# ProPrj___2026-04-10.net
KiCad netlist of a schematic drawn in EasyEDA Pro
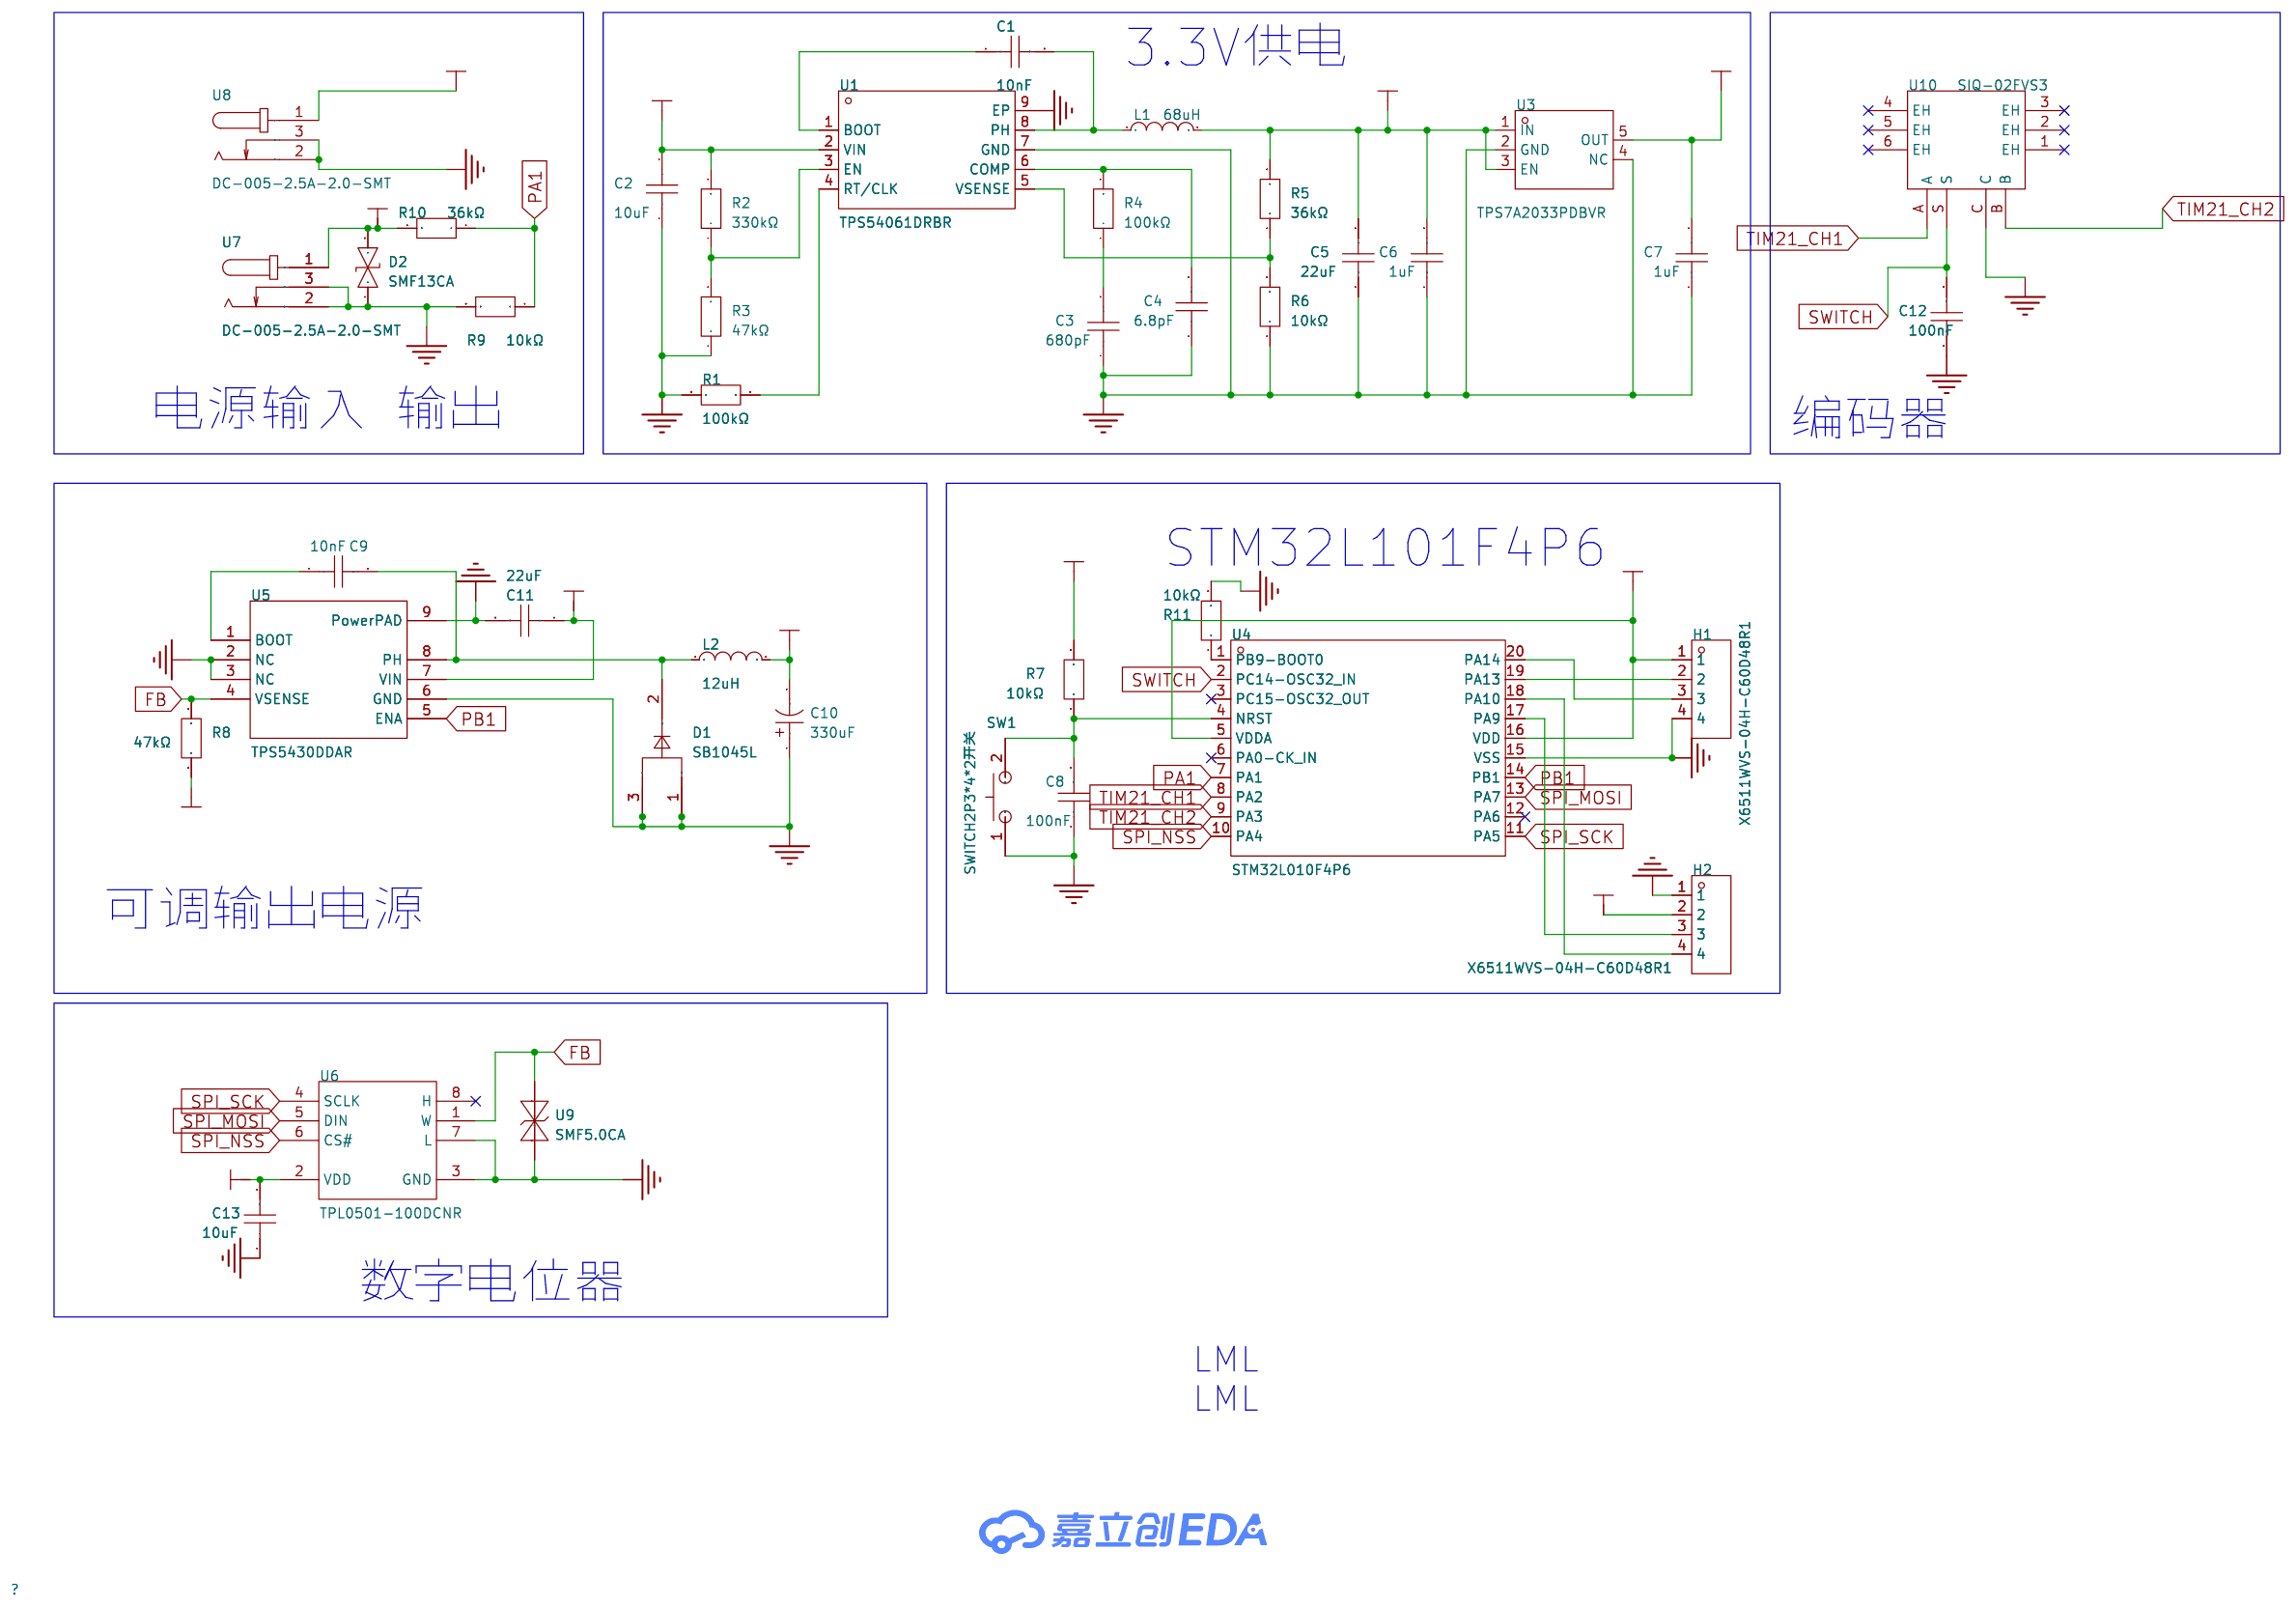
[diagram p0: schematic sheet]

(export (version "E")
  (design (tool "Eeschema 10.0.6"))
  (components
    (comp (ref "C1")
      (value "10nF")
      (footprint "easyedapro:C0603")
      (description "容值:10nF;精度:±10%;额定电压:50V;温度系数:X7R;")
      (fields
        (field (name "Manufacturer Part") "AC0603KPX7R9BB103")
        (field (name "Manufacturer") "YAGEO(国巨)")
      )
      (libsource (lib "easyedapro") (part "AC0603KPX7R9BB103"))
    )
    (comp (ref "C2")
      (value "10uF")
      (footprint "easyedapro:C0603")
      (description "容值:4.7uF;精度:±10%;额定电压:16V;温度系数:X7R;")
      (fields
        (field (name "Manufacturer Part") "GRM188Z71C475KE21J")
        (field (name "Manufacturer") "muRata(村田)")
      )
      (libsource (lib "easyedapro") (part "GRM188Z71C475KE21J"))
    )
    (comp (ref "C3")
      (value "680pF")
      (footprint "easyedapro:C0603")
      (description "容值:4.7uF;精度:±10%;额定电压:16V;温度系数:X7R;")
      (fields
        (field (name "Manufacturer Part") "GRM188Z71C475KE21J")
        (field (name "Manufacturer") "muRata(村田)")
      )
      (libsource (lib "easyedapro") (part "GRM188Z71C475KE21J"))
    )
    (comp (ref "C4")
      (value "6.8pF")
      (footprint "easyedapro:C0603")
      (description "容值:4.7uF;精度:±10%;额定电压:16V;温度系数:X7R;")
      (fields
        (field (name "Manufacturer Part") "GRM188Z71C475KE21J")
        (field (name "Manufacturer") "muRata(村田)")
      )
      (libsource (lib "easyedapro") (part "GRM188Z71C475KE21J"))
    )
    (comp (ref "C5")
      (value "22uF")
      (footprint "easyedapro:C0603")
      (description "容值:4.7uF;精度:±10%;额定电压:16V;温度系数:X7R;")
      (fields
        (field (name "Manufacturer Part") "GRM188Z71C475KE21J")
        (field (name "Manufacturer") "muRata(村田)")
      )
      (libsource (lib "easyedapro") (part "GRM188Z71C475KE21J"))
    )
    (comp (ref "C6")
      (value "1uF")
      (footprint "easyedapro:C0603")
      (description "容值:4.7uF;精度:±10%;额定电压:16V;温度系数:X7R;")
      (fields
        (field (name "Manufacturer Part") "GRM188Z71C475KE21J")
        (field (name "Manufacturer") "muRata(村田)")
      )
      (libsource (lib "easyedapro") (part "GRM188Z71C475KE21J"))
    )
    (comp (ref "C7")
      (value "1uF")
      (footprint "easyedapro:C0603")
      (description "容值:4.7uF;精度:±10%;额定电压:16V;温度系数:X7R;")
      (fields
        (field (name "Manufacturer Part") "GRM188Z71C475KE21J")
        (field (name "Manufacturer") "muRata(村田)")
      )
      (libsource (lib "easyedapro") (part "GRM188Z71C475KE21J"))
    )
    (comp (ref "C8")
      (value "100nF")
      (footprint "easyedapro:C0603")
      (description "容值:10nF;精度:±10%;额定电压:50V;温度系数:X7R;")
      (fields
        (field (name "Manufacturer Part") "AC0603KPX7R9BB103")
        (field (name "Manufacturer") "YAGEO(国巨)")
      )
      (libsource (lib "easyedapro") (part "AC0603KPX7R9BB103"))
    )
    (comp (ref "C9")
      (value "10nF")
      (footprint "easyedapro:C0603")
      (description "容值:10nF;精度:±10%;额定电压:50V;温度系数:X7R;")
      (fields
        (field (name "Manufacturer Part") "AC0603KPX7R9BB103")
        (field (name "Manufacturer") "YAGEO(国巨)")
      )
      (libsource (lib "easyedapro") (part "AC0603KPX7R9BB103"))
    )
    (comp (ref "C10")
      (value "330uF")
      (footprint "easyedapro:CAP-SMD_BD10.0-L10.3-W10.3-SV331M250G12R7R1Z00ZZ")
      (description "容值:330uF;精度:±20%;额定电压:25V;纹波电流:-;等效串联电阻(ESR):-;类型:聚合物;")
      (fields (field (name "Manufacturer Part") "SV331M250G12R7R1Z00ZZ") (field (name "Manufacturer") "创慧电子"))
      (libsource (lib "easyedapro") (part "SV331M250G12R7R1Z00ZZ"))
    )
    (comp (ref "C11")
      (value "22uF")
      (footprint "easyedapro:C0603")
      (description "容值:4.7uF;精度:±10%;额定电压:16V;温度系数:X7R;")
      (fields
        (field (name "Manufacturer Part") "GRM188Z71C475KE21J")
        (field (name "Manufacturer") "muRata(村田)")
      )
      (libsource (lib "easyedapro") (part "GRM188Z71C475KE21J"))
    )
    (comp (ref "C12")
      (value "100nF")
      (footprint "easyedapro:C0603")
      (description "容值:4.7uF;精度:±10%;额定电压:16V;温度系数:X7R;")
      (fields
        (field (name "Manufacturer Part") "GRM188Z71C475KE21J")
        (field (name "Manufacturer") "muRata(村田)")
      )
      (libsource (lib "easyedapro") (part "GRM188Z71C475KE21J"))
    )
    (comp (ref "C13")
      (value "10uF")
      (footprint "easyedapro:C0603")
      (description "容值:4.7uF;精度:±10%;额定电压:16V;温度系数:X7R;")
      (fields
        (field (name "Manufacturer Part") "GRM188Z71C475KE21J")
        (field (name "Manufacturer") "muRata(村田)")
      )
      (libsource (lib "easyedapro") (part "GRM188Z71C475KE21J"))
    )
    (comp (ref "D1")
      (value "SB1045L")
      (footprint "easyedapro:TO-277_3P-L5.4-W4.0-LS6.5-TR")
      (description "二极管配置:独立式;正向压降(Vf):530mV@10A;直流反向耐压(Vr):45V;整流电流:10A;")
      (fields (field (name "Manufacturer") "HXY MOSFET(华轩阳电子)"))
      (libsource (lib "easyedapro") (part "SB1045L_C5199106"))
    )
    (comp (ref "D2")
      (value "SMF13CA")
      (footprint "easyedapro:SOD-123FL_L2.7-W1.8-LS3.8-BI")
      (description "极性:双向;反向截止电压(Vrwm):16V;钳位电压:26V;峰值脉冲电流(Ipp):7.7A@10/1000us;峰值脉冲功率(Ppp):200W@10/1000us;击穿电压:19.7V;")
      (fields (field (name "Manufacturer") "R+O(宏嘉诚)"))
      (libsource (lib "easyedapro") (part "SMF16CA_C2687843"))
    )
    (comp (ref "H1")
      (value "X6511WVS-04H-C60D48R1")
      (footprint "easyedapro:HDR-TH_4P-P2.54-V-F")
      (fields (field (name "Manufacturer") "XKB Connection(中国星坤)"))
      (libsource (lib "easyedapro") (part "2.54-1*4P母"))
    )
    (comp (ref "H2")
      (value "X6511WVS-04H-C60D48R1")
      (footprint "easyedapro:HDR-TH_4P-P2.54-V-F")
      (fields (field (name "Manufacturer") "XKB Connection(中国星坤)"))
      (libsource (lib "easyedapro") (part "2.54-1*4P母"))
    )
    (comp (ref "L1")
      (value "68uH")
      (footprint "easyedapro:IND-SMD_L7.8-W7.0_784787680")
      (description "电感值:68uH;精度:±25%;饱和电流(Isat):1A;")
      (fields (field (name "Manufacturer Part") "784787680") (field (name "Manufacturer") "Wurth(伍尔特)"))
      (libsource (lib "easyedapro") (part "784787680"))
    )
    (comp (ref "L2")
      (value "12uH")
      (footprint "easyedapro:IND-SMD_L12.0-W12.0_744771008")
      (description "电感值:12uH;精度:±20%;额定电流:3.91A;饱和电流(Isat):4.85A;")
      (fields (field (name "Manufacturer Part") "744771112") (field (name "Manufacturer") "Wurth(伍尔特)"))
      (libsource (lib "easyedapro") (part "744771112"))
    )
    (comp (ref "R1")
      (value "100kΩ")
      (footprint "easyedapro:R0603")
      (description "电阻类型:厚膜电阻;阻值:180kΩ;精度:±1%;功率:100mW;工作电压:75V;温度系数:±100ppm/°C;")
      (fields
        (field (name "Manufacturer Part") "GR0603F180KT5G00")
        (field (name "Manufacturer") "GiantOhm(鼎声微电)")
      )
      (libsource (lib "easyedapro") (part "GR0603F180KT5G00"))
    )
    (comp (ref "R2")
      (value "330kΩ")
      (footprint "easyedapro:R0603")
      (description "电阻类型:厚膜电阻;阻值:180kΩ;精度:±1%;功率:100mW;工作电压:75V;温度系数:±100ppm/°C;")
      (fields
        (field (name "Manufacturer Part") "GR0603F180KT5G00")
        (field (name "Manufacturer") "GiantOhm(鼎声微电)")
      )
      (libsource (lib "easyedapro") (part "GR0603F180KT5G00"))
    )
    (comp (ref "R3")
      (value "47kΩ")
      (footprint "easyedapro:R0603")
      (description "电阻类型:厚膜电阻;阻值:180kΩ;精度:±1%;功率:100mW;工作电压:75V;温度系数:±100ppm/°C;")
      (fields
        (field (name "Manufacturer Part") "GR0603F180KT5G00")
        (field (name "Manufacturer") "GiantOhm(鼎声微电)")
      )
      (libsource (lib "easyedapro") (part "GR0603F180KT5G00"))
    )
    (comp (ref "R4")
      (value "100kΩ")
      (footprint "easyedapro:R0603")
      (description "电阻类型:厚膜电阻;阻值:180kΩ;精度:±1%;功率:100mW;工作电压:75V;温度系数:±100ppm/°C;")
      (fields
        (field (name "Manufacturer Part") "GR0603F180KT5G00")
        (field (name "Manufacturer") "GiantOhm(鼎声微电)")
      )
      (libsource (lib "easyedapro") (part "GR0603F180KT5G00"))
    )
    (comp (ref "R5")
      (value "36kΩ")
      (footprint "easyedapro:R0603")
      (description "电阻类型:厚膜电阻;阻值:180kΩ;精度:±1%;功率:100mW;工作电压:75V;温度系数:±100ppm/°C;")
      (fields
        (field (name "Manufacturer Part") "GR0603F180KT5G00")
        (field (name "Manufacturer") "GiantOhm(鼎声微电)")
      )
      (libsource (lib "easyedapro") (part "GR0603F180KT5G00"))
    )
    (comp (ref "R6")
      (value "10kΩ")
      (footprint "easyedapro:R0603")
      (description "电阻类型:厚膜电阻;阻值:180kΩ;精度:±1%;功率:100mW;工作电压:75V;温度系数:±100ppm/°C;")
      (fields
        (field (name "Manufacturer Part") "GR0603F180KT5G00")
        (field (name "Manufacturer") "GiantOhm(鼎声微电)")
      )
      (libsource (lib "easyedapro") (part "GR0603F180KT5G00"))
    )
    (comp (ref "R7")
      (value "10kΩ")
      (footprint "easyedapro:R0603")
      (description "电阻类型:厚膜电阻;阻值:180kΩ;精度:±1%;功率:100mW;工作电压:75V;温度系数:±100ppm/°C;")
      (fields
        (field (name "Manufacturer Part") "GR0603F180KT5G00")
        (field (name "Manufacturer") "GiantOhm(鼎声微电)")
      )
      (libsource (lib "easyedapro") (part "GR0603F180KT5G00"))
    )
    (comp (ref "R8")
      (value "47kΩ")
      (footprint "easyedapro:R0603")
      (description "电阻类型:厚膜电阻;阻值:180kΩ;精度:±1%;功率:100mW;工作电压:75V;温度系数:±100ppm/°C;")
      (fields
        (field (name "Manufacturer Part") "GR0603F180KT5G00")
        (field (name "Manufacturer") "GiantOhm(鼎声微电)")
      )
      (libsource (lib "easyedapro") (part "GR0603F180KT5G00"))
    )
    (comp (ref "R9")
      (value "10kΩ")
      (footprint "easyedapro:R0603")
      (description "电阻类型:厚膜电阻;阻值:180kΩ;精度:±1%;功率:100mW;工作电压:75V;温度系数:±100ppm/°C;")
      (fields
        (field (name "Manufacturer Part") "GR0603F180KT5G00")
        (field (name "Manufacturer") "GiantOhm(鼎声微电)")
      )
      (libsource (lib "easyedapro") (part "GR0603F180KT5G00"))
    )
    (comp (ref "R10")
      (value "36kΩ")
      (footprint "easyedapro:R0603")
      (description "电阻类型:厚膜电阻;阻值:180kΩ;精度:±1%;功率:100mW;工作电压:75V;温度系数:±100ppm/°C;")
      (fields
        (field (name "Manufacturer Part") "GR0603F180KT5G00")
        (field (name "Manufacturer") "GiantOhm(鼎声微电)")
      )
      (libsource (lib "easyedapro") (part "GR0603F180KT5G00"))
    )
    (comp (ref "R11")
      (value "10kΩ")
      (footprint "easyedapro:R0603")
      (description "电阻类型:厚膜电阻;阻值:180kΩ;精度:±1%;功率:100mW;工作电压:75V;温度系数:±100ppm/°C;")
      (fields
        (field (name "Manufacturer Part") "GR0603F180KT5G00")
        (field (name "Manufacturer") "GiantOhm(鼎声微电)")
      )
      (libsource (lib "easyedapro") (part "GR0603F180KT5G00"))
    )
    (comp (ref "SW1")
      (value "SWITCH2P3*4*2开关")
      (footprint "easyedapro:SW-SMD_L3.9-W2.9-P4.15-LS5.0-EH")
      (libsource (lib "easyedapro") (part "SWITCH2P3*4*2开关"))
    )
    (comp (ref "U1")
      (value "TPS54061DRBR")
      (footprint "easyedapro:SON-8_L3.0-W3.0-P0.65-TL-EP")
      (description "功能类型:降压型;输出类型:可调;工作电压:4.7V~60V;输出电压:800mV~58V;输出电流:200mA;")
      (fields (field (name "Manufacturer") "TI(德州仪器)"))
      (libsource (lib "easyedapro") (part "TPS54061DRBR"))
    )
    (comp (ref "U3")
      (value "TPS7A2033PDBVR")
      (footprint "easyedapro:SOT-23-5_L2.9-W1.6-P0.95-LS2.8-BR")
      (description "输出类型:固定;最大输入电压:6V;输出电压:3.3V;输出电流:300mA;输出极性:正极;")
      (fields (field (name "Manufacturer") "TI(德州仪器)"))
      (libsource (lib "easyedapro") (part "TPS7A2033PDBVR"))
    )
    (comp (ref "U4")
      (value "STM32L010F4P6")
      (footprint "easyedapro:TSSOP-20_L6.5-W4.4-P0.65-LS6.4-BL")
      (description "CPU内核:ARM-M系列;CPU最大主频:32MHz;应用领域:-;")
      (fields (field (name "Manufacturer") "ST(意法半导体)"))
      (libsource (lib "easyedapro") (part "STM32L010F4P6"))
    )
    (comp (ref "U5")
      (value "TPS5430DDAR")
      (footprint "easyedapro:ESOP-8_L4.9-W3.9-P1.27-LS6.0-TL-EP")
      (description "功能类型:降压型;工作电压:5.5V~36V;输出电压:1.221V~32.04V;输出电流:3A;输出类型:可调;")
      (fields (field (name "Manufacturer") "TI(德州仪器)"))
      (libsource (lib "easyedapro") (part "TPS5430DDAR"))
    )
    (comp (ref "U6")
      (value "TPL0501-100DCNR")
      (footprint "easyedapro:SOT-23-8_L3.0-W1.7-P0.65-LS2.8-BL")
      (description "电阻值(欧姆):100kΩ;接口类型:SPI;供电电压:2.7V~5.5V;精度:±20%;")
      (fields (field (name "Manufacturer") "TI(德州仪器)"))
      (libsource (lib "easyedapro") (part "TPL0501-100DCNR"))
    )
    (comp (ref "U7")
      (value "DC-005-2.5A-2.0-SMT")
      (footprint "easyedapro:DC-IN-TH_XKB_DC-005-2.5A-2.5-SMT")
      (description "连接器类型:DC电源插座;安装方式:卧贴;触点内径:2mm;触点外径:6.5mm;额定电流:2.5A;额定电压:24V;工作温度:-;")
      (fields (field (name "Manufacturer") "XKB Connection(中国星坤)"))
      (libsource (lib "easyedapro") (part "DC-005-2.5A-2.0-SMT"))
    )
    (comp (ref "U8")
      (value "DC-005-2.5A-2.0-SMT")
      (footprint "easyedapro:DC-IN-TH_XKB_DC-005-2.5A-2.5-SMT")
      (description "连接器类型:DC电源插座;安装方式:卧贴;触点内径:2mm;触点外径:6.5mm;额定电流:2.5A;额定电压:24V;工作温度:-;")
      (fields (field (name "Manufacturer") "XKB Connection(中国星坤)"))
      (libsource (lib "easyedapro") (part "DC-005-2.5A-2.0-SMT"))
    )
    (comp (ref "U9")
      (value "SMF5.0CA")
      (footprint "easyedapro:SOD-123FL_L2.8-W1.8-LS3.7-BI")
      (description "反向截止电压(Vrwm):5V;最大钳位电压:9.2V;峰值脉冲电流(Ipp):21.7A;峰值脉冲功率(Ppp):200W;击穿电压:6.4V;")
      (fields (field (name "Manufacturer") "KUU"))
      (libsource (lib "easyedapro") (part "SMF5.0CA_C2985633"))
    )
    (comp (ref "U10")
      (value "SIQ-02FVS3")
      (footprint "easyedapro:SW-SMD_SIQ-02FVS3_1")
      (fields (field (name "Manufacturer") "MITSUMI(美上美)"))
      (libsource (lib "easyedapro") (part "SIQ-02FVS3"))
    )
  )
  (nets
    (net (code "1") (name "+3.3V") (class "Default")
      (node (ref "C13") (pin "2") (pinfunction "2_2") (pintype "unspecified"))
      (node (ref "C7") (pin "2") (pinfunction "2_2") (pintype "unspecified"))
      (node (ref "H1") (pin "1") (pinfunction "1_1") (pintype "unspecified"))
      (node (ref "H2") (pin "2") (pinfunction "2_2") (pintype "unspecified"))
      (node (ref "R7") (pin "2") (pinfunction "2_2") (pintype "unspecified"))
      (node (ref "U3") (pin "5") (pinfunction "OUT_5") (pintype "unspecified"))
      (node (ref "U4") (pin "16") (pinfunction "VDD_16") (pintype "unspecified"))
      (node (ref "U4") (pin "5") (pinfunction "VDDA_5") (pintype "unspecified"))
      (node (ref "U6") (pin "2") (pinfunction "VDD_2") (pintype "unspecified"))
    )
    (net (code "2") (name "+3.6V") (class "Default")
      (node (ref "C5") (pin "2") (pinfunction "2_2") (pintype "unspecified"))
      (node (ref "C6") (pin "2") (pinfunction "2_2") (pintype "unspecified"))
      (node (ref "L1") (pin "2") (pinfunction "2_2") (pintype "unspecified"))
      (node (ref "R5") (pin "2") (pinfunction "2_2") (pintype "unspecified"))
      (node (ref "U3") (pin "1") (pinfunction "IN_1") (pintype "unspecified"))
      (node (ref "U3") (pin "3") (pinfunction "EN_3") (pintype "unspecified"))
    )
    (net (code "3") (name "+8V") (class "Default")
      (node (ref "C10") (pin "2") (pinfunction "2_2") (pintype "input"))
      (node (ref "D2") (pin "2") (pinfunction "A_2") (pintype "unspecified"))
      (node (ref "L2") (pin "2") (pinfunction "2_2") (pintype "unspecified"))
      (node (ref "R10") (pin "2") (pinfunction "2_2") (pintype "unspecified"))
      (node (ref "R8") (pin "1") (pinfunction "1_1") (pintype "unspecified"))
      (node (ref "U7") (pin "1") (pinfunction "1_1") (pintype "unspecified"))
    )
    (net (code "4") (name "+12V") (class "Default")
      (node (ref "C11") (pin "1") (pinfunction "1_1") (pintype "unspecified"))
      (node (ref "C2") (pin "2") (pinfunction "2_2") (pintype "unspecified"))
      (node (ref "R2") (pin "2") (pinfunction "2_2") (pintype "unspecified"))
      (node (ref "U1") (pin "2") (pinfunction "VIN_2") (pintype "unspecified"))
      (node (ref "U5") (pin "7") (pinfunction "VIN_7") (pintype "unspecified"))
      (node (ref "U8") (pin "1") (pinfunction "1_1") (pintype "unspecified"))
    )
    (net (code "5") (name "FB") (class "Default")
      (node (ref "R8") (pin "2") (pinfunction "2_2") (pintype "unspecified"))
      (node (ref "U5") (pin "4") (pinfunction "VSENSE_4") (pintype "unspecified"))
      (node (ref "U6") (pin "1") (pinfunction "W_1") (pintype "unspecified"))
      (node (ref "U9") (pin "2") (pinfunction "2_2") (pintype "unspecified"))
    )
    (net (code "6") (name "GND") (class "Default")
      (node (ref "C10") (pin "1") (pinfunction "1_1") (pintype "input"))
      (node (ref "C11") (pin "2") (pinfunction "2_2") (pintype "unspecified"))
      (node (ref "C12") (pin "1") (pinfunction "1_1") (pintype "unspecified"))
      (node (ref "C13") (pin "1") (pinfunction "1_1") (pintype "unspecified"))
      (node (ref "C2") (pin "1") (pinfunction "1_1") (pintype "unspecified"))
      (node (ref "C3") (pin "1") (pinfunction "1_1") (pintype "unspecified"))
      (node (ref "C4") (pin "1") (pinfunction "1_1") (pintype "unspecified"))
      (node (ref "C5") (pin "1") (pinfunction "1_1") (pintype "unspecified"))
      (node (ref "C6") (pin "1") (pinfunction "1_1") (pintype "unspecified"))
      (node (ref "C7") (pin "1") (pinfunction "1_1") (pintype "unspecified"))
      (node (ref "C8") (pin "1") (pinfunction "1_1") (pintype "unspecified"))
      (node (ref "D1") (pin "1") (pinfunction "A_1") (pintype "unspecified"))
      (node (ref "D1") (pin "3") (pinfunction "A_3") (pintype "unspecified"))
      (node (ref "D2") (pin "1") (pinfunction "K_1") (pintype "unspecified"))
      (node (ref "H1") (pin "4") (pinfunction "4_4") (pintype "unspecified"))
      (node (ref "H2") (pin "1") (pinfunction "1_1") (pintype "unspecified"))
      (node (ref "R1") (pin "1") (pinfunction "1_1") (pintype "unspecified"))
      (node (ref "R11") (pin "2") (pinfunction "2_2") (pintype "unspecified"))
      (node (ref "R3") (pin "1") (pinfunction "1_1") (pintype "unspecified"))
      (node (ref "R6") (pin "1") (pinfunction "1_1") (pintype "unspecified"))
      (node (ref "R9") (pin "2") (pinfunction "2_2") (pintype "unspecified"))
      (node (ref "SW1") (pin "1") (pinfunction "1_1") (pintype "unspecified"))
      (node (ref "U1") (pin "7") (pinfunction "GND_7") (pintype "unspecified"))
      (node (ref "U1") (pin "9") (pinfunction "EP_9") (pintype "unspecified"))
      (node (ref "U10") (pin "C") (pinfunction "C_C") (pintype "unspecified"))
      (node (ref "U3") (pin "2") (pinfunction "GND_2") (pintype "unspecified"))
      (node (ref "U3") (pin "4") (pinfunction "NC_4") (pintype "unspecified"))
      (node (ref "U4") (pin "15") (pinfunction "VSS_15") (pintype "unspecified"))
      (node (ref "U5") (pin "2") (pinfunction "NC_2") (pintype "unspecified"))
      (node (ref "U5") (pin "3") (pinfunction "NC_3") (pintype "unspecified"))
      (node (ref "U5") (pin "6") (pinfunction "GND_6") (pintype "unspecified"))
      (node (ref "U5") (pin "9") (pinfunction "PowerPAD_9") (pintype "unspecified"))
      (node (ref "U6") (pin "3") (pinfunction "GND_3") (pintype "unspecified"))
      (node (ref "U6") (pin "7") (pinfunction "L_7") (pintype "unspecified"))
      (node (ref "U7") (pin "2") (pinfunction "2_2") (pintype "unspecified"))
      (node (ref "U7") (pin "3") (pinfunction "3_3") (pintype "unspecified"))
      (node (ref "U8") (pin "2") (pinfunction "2_2") (pintype "unspecified"))
      (node (ref "U8") (pin "3") (pinfunction "3_3") (pintype "unspecified"))
      (node (ref "U9") (pin "1") (pinfunction "1_1") (pintype "unspecified"))
    )
    (net (code "7") (name "Net-(C3-Pad2)") (class "Default")
      (node (ref "C3") (pin "2") (pinfunction "2_2") (pintype "unspecified"))
      (node (ref "R4") (pin "1") (pinfunction "1_1") (pintype "unspecified"))
    )
    (net (code "8") (name "Net-(D1-C)") (class "Default")
      (node (ref "C9") (pin "2") (pinfunction "2_2") (pintype "unspecified"))
      (node (ref "D1") (pin "2") (pinfunction "C_2") (pintype "unspecified"))
      (node (ref "L2") (pin "1") (pinfunction "1_1") (pintype "unspecified"))
      (node (ref "U5") (pin "8") (pinfunction "PH_8") (pintype "unspecified"))
    )
    (net (code "9") (name "Net-(U1-BOOT)") (class "Default")
      (node (ref "C1") (pin "1") (pinfunction "1_1") (pintype "unspecified"))
      (node (ref "U1") (pin "1") (pinfunction "BOOT_1") (pintype "unspecified"))
    )
    (net (code "10") (name "Net-(U1-COMP)") (class "Default")
      (node (ref "C4") (pin "2") (pinfunction "2_2") (pintype "unspecified"))
      (node (ref "R4") (pin "2") (pinfunction "2_2") (pintype "unspecified"))
      (node (ref "U1") (pin "6") (pinfunction "COMP_6") (pintype "unspecified"))
    )
    (net (code "11") (name "Net-(U1-EN)") (class "Default")
      (node (ref "R2") (pin "1") (pinfunction "1_1") (pintype "unspecified"))
      (node (ref "R3") (pin "2") (pinfunction "2_2") (pintype "unspecified"))
      (node (ref "U1") (pin "3") (pinfunction "EN_3") (pintype "unspecified"))
    )
    (net (code "12") (name "Net-(U1-PH)") (class "Default")
      (node (ref "C1") (pin "2") (pinfunction "2_2") (pintype "unspecified"))
      (node (ref "L1") (pin "1") (pinfunction "1_1") (pintype "unspecified"))
      (node (ref "U1") (pin "8") (pinfunction "PH_8") (pintype "unspecified"))
    )
    (net (code "13") (name "Net-(U1-RT{slash}CLK)") (class "Default")
      (node (ref "R1") (pin "2") (pinfunction "2_2") (pintype "unspecified"))
      (node (ref "U1") (pin "4") (pinfunction "RT/CLK_4") (pintype "unspecified"))
    )
    (net (code "14") (name "Net-(U1-VSENSE)") (class "Default")
      (node (ref "R5") (pin "1") (pinfunction "1_1") (pintype "unspecified"))
      (node (ref "R6") (pin "2") (pinfunction "2_2") (pintype "unspecified"))
      (node (ref "U1") (pin "5") (pinfunction "VSENSE_5") (pintype "unspecified"))
    )
    (net (code "15") (name "Net-(U4-NRST)") (class "Default")
      (node (ref "C8") (pin "2") (pinfunction "2_2") (pintype "unspecified"))
      (node (ref "R7") (pin "1") (pinfunction "1_1") (pintype "unspecified"))
      (node (ref "SW1") (pin "2") (pinfunction "2_2") (pintype "unspecified"))
      (node (ref "U4") (pin "4") (pinfunction "NRST_4") (pintype "unspecified"))
    )
    (net (code "16") (name "Net-(U4-PA9)") (class "Default")
      (node (ref "H2") (pin "3") (pinfunction "3_3") (pintype "unspecified"))
      (node (ref "U4") (pin "17") (pinfunction "PA9_17") (pintype "unspecified"))
    )
    (net (code "17") (name "Net-(U4-PA10)") (class "Default")
      (node (ref "H2") (pin "4") (pinfunction "4_4") (pintype "unspecified"))
      (node (ref "U4") (pin "18") (pinfunction "PA10_18") (pintype "unspecified"))
    )
    (net (code "18") (name "Net-(U4-PA13)") (class "Default")
      (node (ref "H1") (pin "2") (pinfunction "2_2") (pintype "unspecified"))
      (node (ref "U4") (pin "19") (pinfunction "PA13_19") (pintype "unspecified"))
    )
    (net (code "19") (name "Net-(U4-PA14)") (class "Default")
      (node (ref "H1") (pin "3") (pinfunction "3_3") (pintype "unspecified"))
      (node (ref "U4") (pin "20") (pinfunction "PA14_20") (pintype "unspecified"))
    )
    (net (code "20") (name "Net-(U4-PB9-BOOT0)") (class "Default")
      (node (ref "R11") (pin "1") (pinfunction "1_1") (pintype "unspecified"))
      (node (ref "U4") (pin "1") (pinfunction "PB9-BOOT0_1") (pintype "unspecified"))
    )
    (net (code "21") (name "Net-(U5-BOOT)") (class "Default")
      (node (ref "C9") (pin "1") (pinfunction "1_1") (pintype "unspecified"))
      (node (ref "U5") (pin "1") (pinfunction "BOOT_1") (pintype "unspecified"))
    )
    (net (code "22") (name "PA1") (class "Default")
      (node (ref "R10") (pin "1") (pinfunction "1_1") (pintype "unspecified"))
      (node (ref "R9") (pin "1") (pinfunction "1_1") (pintype "unspecified"))
      (node (ref "U4") (pin "7") (pinfunction "PA1_7") (pintype "unspecified"))
    )
    (net (code "23") (name "PB1") (class "Default")
      (node (ref "U4") (pin "14") (pinfunction "PB1_14") (pintype "unspecified"))
      (node (ref "U5") (pin "5") (pinfunction "ENA_5") (pintype "unspecified"))
    )
    (net (code "24") (name "SPI_MOSI") (class "Default")
      (node (ref "U4") (pin "13") (pinfunction "PA7_13") (pintype "unspecified"))
      (node (ref "U6") (pin "5") (pinfunction "DIN_5") (pintype "unspecified"))
    )
    (net (code "25") (name "SPI_NSS") (class "Default")
      (node (ref "U4") (pin "10") (pinfunction "PA4_10") (pintype "unspecified"))
      (node (ref "U6") (pin "6") (pinfunction "CS#_6") (pintype "unspecified"))
    )
    (net (code "26") (name "SPI_SCK") (class "Default")
      (node (ref "U4") (pin "11") (pinfunction "PA5_11") (pintype "unspecified"))
      (node (ref "U6") (pin "4") (pinfunction "SCLK_4") (pintype "unspecified"))
    )
    (net (code "27") (name "SWITCH") (class "Default")
      (node (ref "C12") (pin "2") (pinfunction "2_2") (pintype "unspecified"))
      (node (ref "U10") (pin "S") (pinfunction "S_S") (pintype "unspecified"))
      (node (ref "U4") (pin "2") (pinfunction "PC14-OSC32_IN_2") (pintype "unspecified"))
    )
    (net (code "28") (name "TIM21_CH1") (class "Default")
      (node (ref "U10") (pin "A") (pinfunction "A_A") (pintype "unspecified"))
      (node (ref "U4") (pin "8") (pinfunction "PA2_8") (pintype "unspecified"))
    )
    (net (code "29") (name "TIM21_CH2") (class "Default")
      (node (ref "U10") (pin "B") (pinfunction "B_B") (pintype "unspecified"))
      (node (ref "U4") (pin "9") (pinfunction "PA3_9") (pintype "unspecified"))
    )
    (net (code "30") (name "unconnected-(U4-PA0-CK_IN-Pad6)") (class "Default")
      (node (ref "U4") (pin "6") (pinfunction "PA0-CK_IN_6") (pintype "unspecified+no_connect"))
    )
    (net (code "31") (name "unconnected-(U4-PA6-Pad12)") (class "Default")
      (node (ref "U4") (pin "12") (pinfunction "PA6_12") (pintype "unspecified+no_connect"))
    )
    (net (code "32") (name "unconnected-(U4-PC15-OSC32_OUT-Pad3)") (class "Default")
      (node (ref "U4") (pin "3") (pinfunction "PC15-OSC32_OUT_3") (pintype "unspecified+no_connect"))
    )
    (net (code "33") (name "unconnected-(U6-H-Pad8)") (class "Default")
      (node (ref "U6") (pin "8") (pinfunction "H_8") (pintype "unspecified+no_connect"))
    )
    (net (code "34") (name "unconnected-(U10-EH-Pad1)") (class "Default")
      (node (ref "U10") (pin "1") (pinfunction "EH_1") (pintype "unspecified+no_connect"))
    )
    (net (code "35") (name "unconnected-(U10-EH-Pad2)") (class "Default")
      (node (ref "U10") (pin "2") (pinfunction "EH_2") (pintype "unspecified+no_connect"))
    )
    (net (code "36") (name "unconnected-(U10-EH-Pad3)") (class "Default")
      (node (ref "U10") (pin "3") (pinfunction "EH_3") (pintype "unspecified+no_connect"))
    )
    (net (code "37") (name "unconnected-(U10-EH-Pad4)") (class "Default")
      (node (ref "U10") (pin "4") (pinfunction "EH_4") (pintype "unspecified+no_connect"))
    )
    (net (code "38") (name "unconnected-(U10-EH-Pad5)") (class "Default")
      (node (ref "U10") (pin "5") (pinfunction "EH_5") (pintype "unspecified+no_connect"))
    )
    (net (code "39") (name "unconnected-(U10-EH-Pad6)") (class "Default")
      (node (ref "U10") (pin "6") (pinfunction "EH_6") (pintype "unspecified+no_connect"))
    )
  )
)
